# Dumb-E.net
KiCad netlist of a schematic drawn in EAGLE
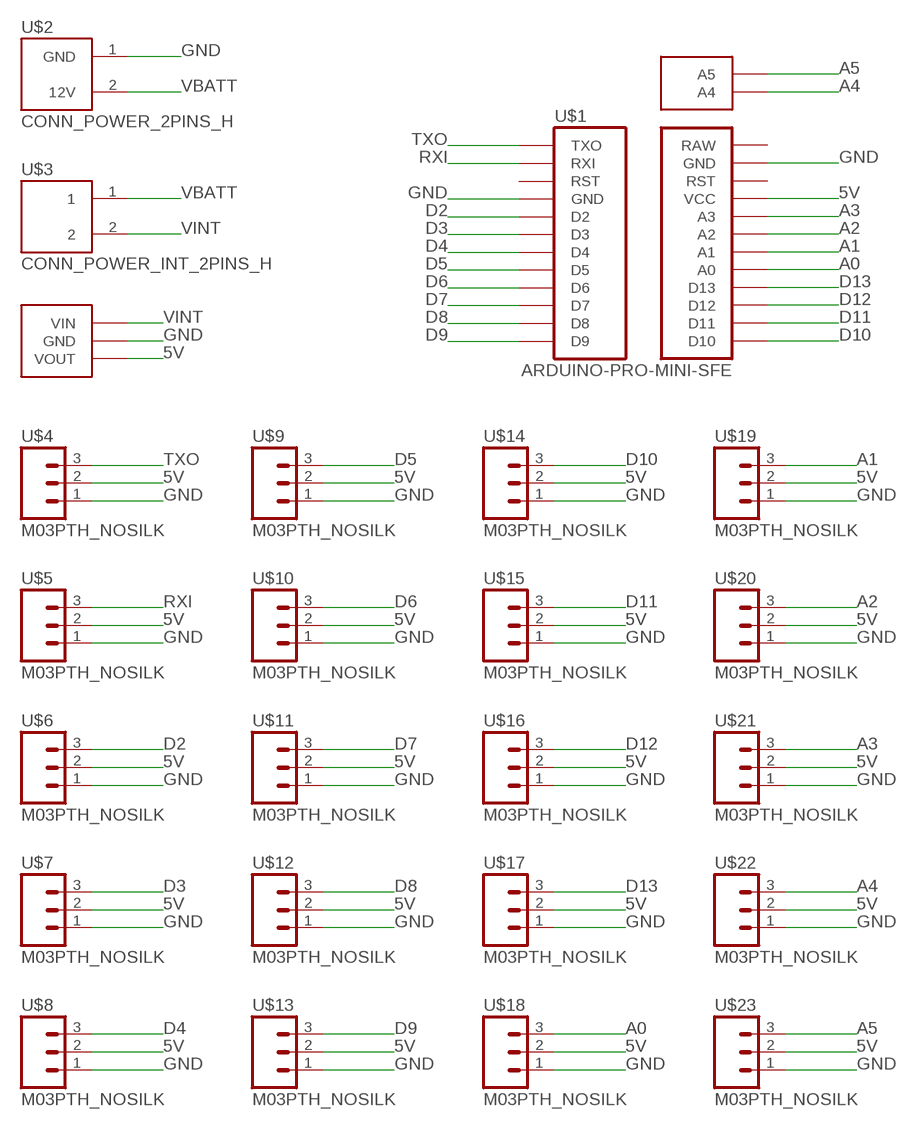
[diagram p0: schematic, sheet 1]

(export (version "E")
  (design (tool "Eeschema 10.0.6"))
  (components
    (comp (ref "U$1")
      (value "ARDUINO-PRO-MINI-SFE")
      (footprint "eagle-import:ARDUINO-PRO-MINI")
      (libsource (lib "eagle-import") (part "ARDUINO-PRO-MINI-SFE"))
    )
    (comp (ref "U$2")
      (value "CONN_POWER_2PINS_H")
      (footprint "eagle-import:2PINS_5MM_90DEG")
      (libsource (lib "eagle-import") (part "CONN_POWER_2PINS_H"))
    )
    (comp (ref "U$3")
      (value "CONN_POWER_INT_2PINS_H")
      (footprint "eagle-import:2PINS_5MM_90DEG")
      (libsource (lib "eagle-import") (part "CONN_POWER_INT_2PINS_H"))
    )
    (comp (ref "U$4")
      (value "M03PTH_NOSILK")
      (footprint "eagle-import:1X03_NOSILK")
      (libsource (lib "eagle-import") (part "M03PTH_NOSILK"))
    )
    (comp (ref "U$5")
      (value "M03PTH_NOSILK")
      (footprint "eagle-import:1X03_NOSILK")
      (libsource (lib "eagle-import") (part "M03PTH_NOSILK"))
    )
    (comp (ref "U$6")
      (value "M03PTH_NOSILK")
      (footprint "eagle-import:1X03_NOSILK")
      (libsource (lib "eagle-import") (part "M03PTH_NOSILK"))
    )
    (comp (ref "U$7")
      (value "M03PTH_NOSILK")
      (footprint "eagle-import:1X03_NOSILK")
      (libsource (lib "eagle-import") (part "M03PTH_NOSILK"))
    )
    (comp (ref "U$8")
      (value "M03PTH_NOSILK")
      (footprint "eagle-import:1X03_NOSILK")
      (libsource (lib "eagle-import") (part "M03PTH_NOSILK"))
    )
    (comp (ref "U$9")
      (value "M03PTH_NOSILK")
      (footprint "eagle-import:1X03_NOSILK")
      (libsource (lib "eagle-import") (part "M03PTH_NOSILK"))
    )
    (comp (ref "U$10")
      (value "M03PTH_NOSILK")
      (footprint "eagle-import:1X03_NOSILK")
      (libsource (lib "eagle-import") (part "M03PTH_NOSILK"))
    )
    (comp (ref "U$11")
      (value "M03PTH_NOSILK")
      (footprint "eagle-import:1X03_NOSILK")
      (libsource (lib "eagle-import") (part "M03PTH_NOSILK"))
    )
    (comp (ref "U$12")
      (value "M03PTH_NOSILK")
      (footprint "eagle-import:1X03_NOSILK")
      (libsource (lib "eagle-import") (part "M03PTH_NOSILK"))
    )
    (comp (ref "U$13")
      (value "M03PTH_NOSILK")
      (footprint "eagle-import:1X03_NOSILK")
      (libsource (lib "eagle-import") (part "M03PTH_NOSILK"))
    )
    (comp (ref "U$14")
      (value "M03PTH_NOSILK")
      (footprint "eagle-import:1X03_NOSILK")
      (libsource (lib "eagle-import") (part "M03PTH_NOSILK"))
    )
    (comp (ref "U$15")
      (value "M03PTH_NOSILK")
      (footprint "eagle-import:1X03_NOSILK")
      (libsource (lib "eagle-import") (part "M03PTH_NOSILK"))
    )
    (comp (ref "U$16")
      (value "M03PTH_NOSILK")
      (footprint "eagle-import:1X03_NOSILK")
      (libsource (lib "eagle-import") (part "M03PTH_NOSILK"))
    )
    (comp (ref "U$17")
      (value "M03PTH_NOSILK")
      (footprint "eagle-import:1X03_NOSILK")
      (libsource (lib "eagle-import") (part "M03PTH_NOSILK"))
    )
    (comp (ref "U$18")
      (value "M03PTH_NOSILK")
      (footprint "eagle-import:1X03_NOSILK")
      (libsource (lib "eagle-import") (part "M03PTH_NOSILK"))
    )
    (comp (ref "U$19")
      (value "M03PTH_NOSILK")
      (footprint "eagle-import:1X03_NOSILK")
      (libsource (lib "eagle-import") (part "M03PTH_NOSILK"))
    )
    (comp (ref "U$20")
      (value "M03PTH_NOSILK")
      (footprint "eagle-import:1X03_NOSILK")
      (libsource (lib "eagle-import") (part "M03PTH_NOSILK"))
    )
    (comp (ref "U$21")
      (value "M03PTH_NOSILK")
      (footprint "eagle-import:1X03_NOSILK")
      (libsource (lib "eagle-import") (part "M03PTH_NOSILK"))
    )
    (comp (ref "U$22")
      (value "M03PTH_NOSILK")
      (footprint "eagle-import:1X03_NOSILK")
      (libsource (lib "eagle-import") (part "M03PTH_NOSILK"))
    )
    (comp (ref "U$23")
      (value "M03PTH_NOSILK")
      (footprint "eagle-import:1X03_NOSILK")
      (libsource (lib "eagle-import") (part "M03PTH_NOSILK"))
    )
    (comp (ref "U$25")
      (value "DE-SW0XX")
      (footprint "eagle-import:DE-SW0XX")
      (libsource (lib "eagle-import") (part "DE-SW0XX"))
    )
  )
  (nets
    (net (code "1") (name "/5V") (class "Default")
      (node (ref "U$1") (pin "P$17") (pinfunction "VCC_P$17") (pintype "passive"))
      (node (ref "U$10") (pin "2") (pinfunction "2_2") (pintype "passive"))
      (node (ref "U$11") (pin "2") (pinfunction "2_2") (pintype "passive"))
      (node (ref "U$12") (pin "2") (pinfunction "2_2") (pintype "passive"))
      (node (ref "U$13") (pin "2") (pinfunction "2_2") (pintype "passive"))
      (node (ref "U$14") (pin "2") (pinfunction "2_2") (pintype "passive"))
      (node (ref "U$15") (pin "2") (pinfunction "2_2") (pintype "passive"))
      (node (ref "U$16") (pin "2") (pinfunction "2_2") (pintype "passive"))
      (node (ref "U$17") (pin "2") (pinfunction "2_2") (pintype "passive"))
      (node (ref "U$18") (pin "2") (pinfunction "2_2") (pintype "passive"))
      (node (ref "U$19") (pin "2") (pinfunction "2_2") (pintype "passive"))
      (node (ref "U$20") (pin "2") (pinfunction "2_2") (pintype "passive"))
      (node (ref "U$21") (pin "2") (pinfunction "2_2") (pintype "passive"))
      (node (ref "U$22") (pin "2") (pinfunction "2_2") (pintype "passive"))
      (node (ref "U$23") (pin "2") (pinfunction "2_2") (pintype "passive"))
      (node (ref "U$25") (pin "VOUT") (pinfunction "VOUT_VOUT") (pintype "passive"))
      (node (ref "U$4") (pin "2") (pinfunction "2_2") (pintype "passive"))
      (node (ref "U$5") (pin "2") (pinfunction "2_2") (pintype "passive"))
      (node (ref "U$6") (pin "2") (pinfunction "2_2") (pintype "passive"))
      (node (ref "U$7") (pin "2") (pinfunction "2_2") (pintype "passive"))
      (node (ref "U$8") (pin "2") (pinfunction "2_2") (pintype "passive"))
      (node (ref "U$9") (pin "2") (pinfunction "2_2") (pintype "passive"))
    )
    (net (code "2") (name "/A0") (class "Default")
      (node (ref "U$1") (pin "P$9") (pinfunction "A0_P$9") (pintype "passive"))
      (node (ref "U$18") (pin "3") (pinfunction "3_3") (pintype "passive"))
    )
    (net (code "3") (name "/A1") (class "Default")
      (node (ref "U$1") (pin "P$11") (pinfunction "A1_P$11") (pintype "passive"))
      (node (ref "U$19") (pin "3") (pinfunction "3_3") (pintype "passive"))
    )
    (net (code "4") (name "/A2") (class "Default")
      (node (ref "U$1") (pin "P$13") (pinfunction "A2_P$13") (pintype "passive"))
      (node (ref "U$20") (pin "3") (pinfunction "3_3") (pintype "passive"))
    )
    (net (code "5") (name "/A3") (class "Default")
      (node (ref "U$1") (pin "P$15") (pinfunction "A3_P$15") (pintype "passive"))
      (node (ref "U$21") (pin "3") (pinfunction "3_3") (pintype "passive"))
    )
    (net (code "6") (name "/A4") (class "Default")
      (node (ref "U$1") (pin "P$26") (pinfunction "A4_P$26") (pintype "passive"))
      (node (ref "U$22") (pin "3") (pinfunction "3_3") (pintype "passive"))
    )
    (net (code "7") (name "/A5") (class "Default")
      (node (ref "U$1") (pin "P$25") (pinfunction "A5_P$25") (pintype "passive"))
      (node (ref "U$23") (pin "3") (pinfunction "3_3") (pintype "passive"))
    )
    (net (code "8") (name "/D2") (class "Default")
      (node (ref "U$1") (pin "P$16") (pinfunction "D2_P$16") (pintype "passive"))
      (node (ref "U$6") (pin "3") (pinfunction "3_3") (pintype "passive"))
    )
    (net (code "9") (name "/D3") (class "Default")
      (node (ref "U$1") (pin "P$14") (pinfunction "D3_P$14") (pintype "passive"))
      (node (ref "U$7") (pin "3") (pinfunction "3_3") (pintype "passive"))
    )
    (net (code "10") (name "/D4") (class "Default")
      (node (ref "U$1") (pin "P$12") (pinfunction "D4_P$12") (pintype "passive"))
      (node (ref "U$8") (pin "3") (pinfunction "3_3") (pintype "passive"))
    )
    (net (code "11") (name "/D5") (class "Default")
      (node (ref "U$1") (pin "P$10") (pinfunction "D5_P$10") (pintype "passive"))
      (node (ref "U$9") (pin "3") (pinfunction "3_3") (pintype "passive"))
    )
    (net (code "12") (name "/D6") (class "Default")
      (node (ref "U$1") (pin "P$8") (pinfunction "D6_P$8") (pintype "passive"))
      (node (ref "U$10") (pin "3") (pinfunction "3_3") (pintype "passive"))
    )
    (net (code "13") (name "/D7") (class "Default")
      (node (ref "U$1") (pin "P$6") (pinfunction "D7_P$6") (pintype "passive"))
      (node (ref "U$11") (pin "3") (pinfunction "3_3") (pintype "passive"))
    )
    (net (code "14") (name "/D8") (class "Default")
      (node (ref "U$1") (pin "P$4") (pinfunction "D8_P$4") (pintype "passive"))
      (node (ref "U$12") (pin "3") (pinfunction "3_3") (pintype "passive"))
    )
    (net (code "15") (name "/D9") (class "Default")
      (node (ref "U$1") (pin "P$2") (pinfunction "D9_P$2") (pintype "passive"))
      (node (ref "U$13") (pin "3") (pinfunction "3_3") (pintype "passive"))
    )
    (net (code "16") (name "/D10") (class "Default")
      (node (ref "U$1") (pin "P$1") (pinfunction "D10_P$1") (pintype "passive"))
      (node (ref "U$14") (pin "3") (pinfunction "3_3") (pintype "passive"))
    )
    (net (code "17") (name "/D11") (class "Default")
      (node (ref "U$1") (pin "P$3") (pinfunction "D11_P$3") (pintype "passive"))
      (node (ref "U$15") (pin "3") (pinfunction "3_3") (pintype "passive"))
    )
    (net (code "18") (name "/D12") (class "Default")
      (node (ref "U$1") (pin "P$5") (pinfunction "D12_P$5") (pintype "passive"))
      (node (ref "U$16") (pin "3") (pinfunction "3_3") (pintype "passive"))
    )
    (net (code "19") (name "/D13") (class "Default")
      (node (ref "U$1") (pin "P$7") (pinfunction "D13_P$7") (pintype "passive"))
      (node (ref "U$17") (pin "3") (pinfunction "3_3") (pintype "passive"))
    )
    (net (code "20") (name "/GND") (class "Default")
      (node (ref "U$1") (pin "P$18") (pinfunction "GND_P$18") (pintype "passive"))
      (node (ref "U$1") (pin "P$21") (pinfunction "GND_P$21") (pintype "passive"))
      (node (ref "U$10") (pin "1") (pinfunction "1_1") (pintype "passive"))
      (node (ref "U$11") (pin "1") (pinfunction "1_1") (pintype "passive"))
      (node (ref "U$12") (pin "1") (pinfunction "1_1") (pintype "passive"))
      (node (ref "U$13") (pin "1") (pinfunction "1_1") (pintype "passive"))
      (node (ref "U$14") (pin "1") (pinfunction "1_1") (pintype "passive"))
      (node (ref "U$15") (pin "1") (pinfunction "1_1") (pintype "passive"))
      (node (ref "U$16") (pin "1") (pinfunction "1_1") (pintype "passive"))
      (node (ref "U$17") (pin "1") (pinfunction "1_1") (pintype "passive"))
      (node (ref "U$18") (pin "1") (pinfunction "1_1") (pintype "passive"))
      (node (ref "U$19") (pin "1") (pinfunction "1_1") (pintype "passive"))
      (node (ref "U$2") (pin "1") (pinfunction "GND_1") (pintype "power_in"))
      (node (ref "U$20") (pin "1") (pinfunction "1_1") (pintype "passive"))
      (node (ref "U$21") (pin "1") (pinfunction "1_1") (pintype "passive"))
      (node (ref "U$22") (pin "1") (pinfunction "1_1") (pintype "passive"))
      (node (ref "U$23") (pin "1") (pinfunction "1_1") (pintype "passive"))
      (node (ref "U$25") (pin "GND") (pinfunction "GND_GND") (pintype "passive"))
      (node (ref "U$4") (pin "1") (pinfunction "1_1") (pintype "passive"))
      (node (ref "U$5") (pin "1") (pinfunction "1_1") (pintype "passive"))
      (node (ref "U$6") (pin "1") (pinfunction "1_1") (pintype "passive"))
      (node (ref "U$7") (pin "1") (pinfunction "1_1") (pintype "passive"))
      (node (ref "U$8") (pin "1") (pinfunction "1_1") (pintype "passive"))
      (node (ref "U$9") (pin "1") (pinfunction "1_1") (pintype "passive"))
    )
    (net (code "21") (name "/RXI") (class "Default")
      (node (ref "U$1") (pin "P$22") (pinfunction "RXI_P$22") (pintype "passive"))
      (node (ref "U$5") (pin "3") (pinfunction "3_3") (pintype "passive"))
    )
    (net (code "22") (name "/TXO") (class "Default")
      (node (ref "U$1") (pin "P$24") (pinfunction "TXO_P$24") (pintype "passive"))
      (node (ref "U$4") (pin "3") (pinfunction "3_3") (pintype "passive"))
    )
    (net (code "23") (name "/VBATT") (class "Default")
      (node (ref "U$2") (pin "2") (pinfunction "12V_2") (pintype "power_in"))
      (node (ref "U$3") (pin "1") (pinfunction "1_1") (pintype "power_in"))
    )
    (net (code "24") (name "/VINT") (class "Default")
      (node (ref "U$25") (pin "VIN") (pinfunction "VIN_VIN") (pintype "passive"))
      (node (ref "U$3") (pin "2") (pinfunction "2_2") (pintype "power_in"))
    )
    (net (code "25") (name "unconnected-(U$1-RAW-PadP$23)") (class "Default")
      (node (ref "U$1") (pin "P$23") (pinfunction "RAW_P$23") (pintype "passive"))
    )
    (net (code "26") (name "unconnected-(U$1-RST-PadP$19)") (class "Default")
      (node (ref "U$1") (pin "P$19") (pinfunction "RST_P$19") (pintype "passive"))
    )
    (net (code "27") (name "unconnected-(U$1-RST-PadP$20)") (class "Default")
      (node (ref "U$1") (pin "P$20") (pinfunction "RST_P$20") (pintype "passive"))
    )
  )
)
